# sch_camera.net
KiCad netlist of a schematic drawn in Altium Designer
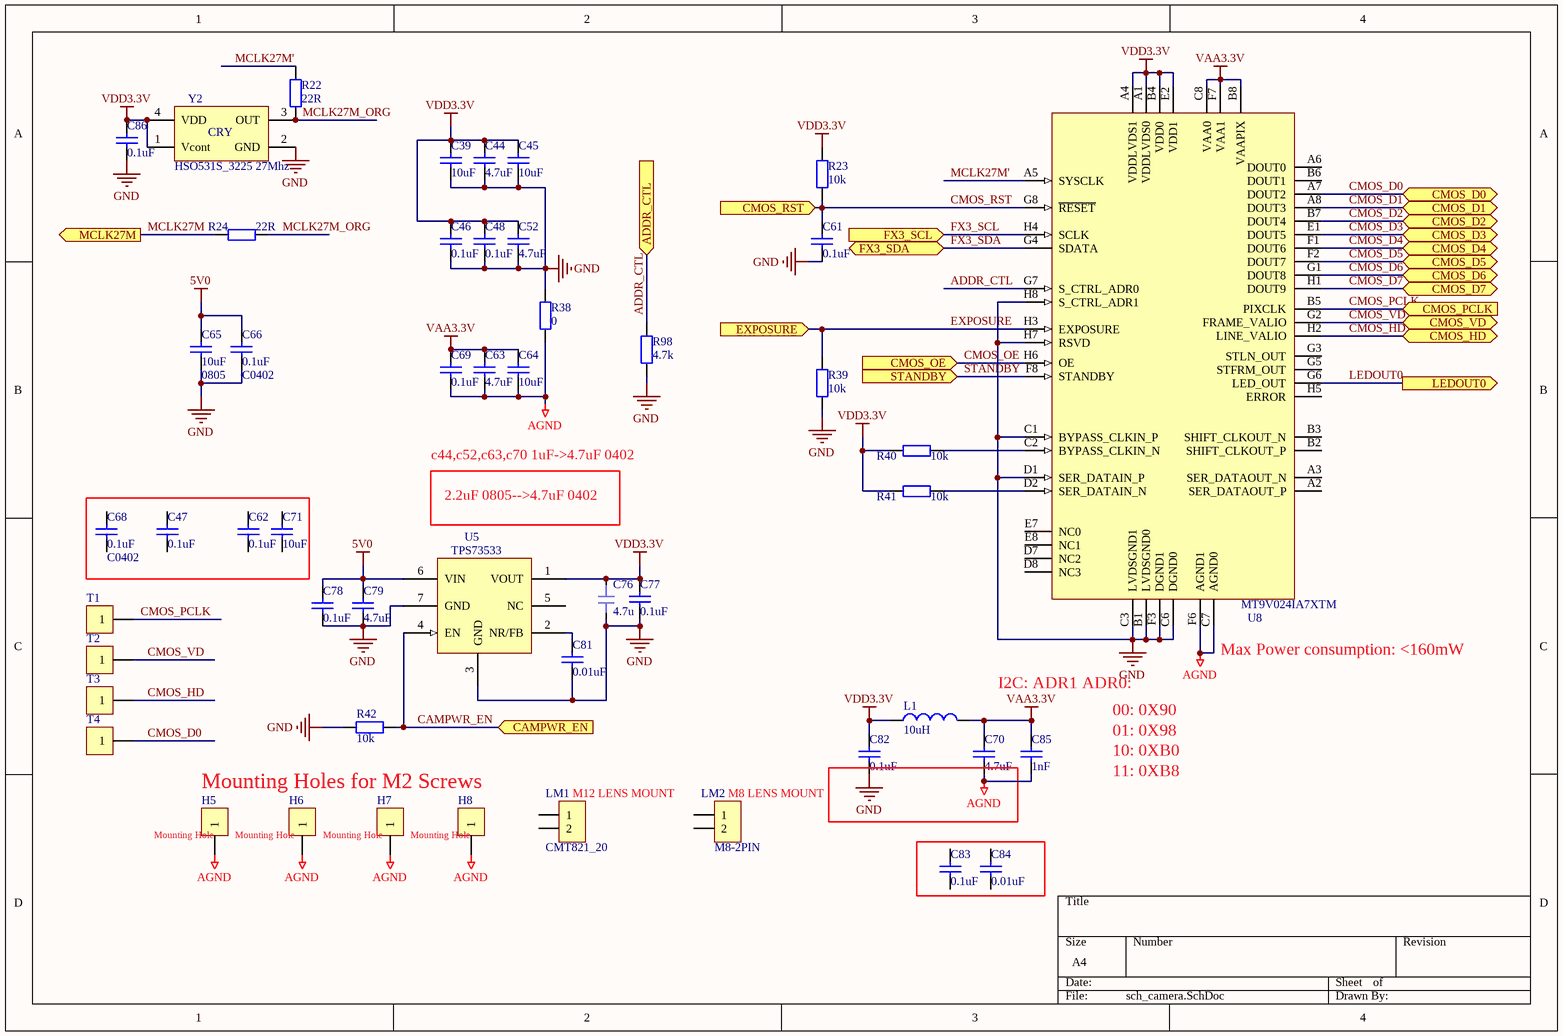
[diagram p0: sch_camera.SchDoc]

(export (version "E")
  (design (tool "Eeschema 10.0.6"))
  (components
    (comp (ref "C39")
      (value "10uF")
      (footprint "0805C")
      (description "Capacitor")
      (fields (field (name "PUBLISHER") "Altium Limited"))
      (libsource (lib "Miscellaneous Devices") (part "Cap"))
    )
    (comp (ref "C44")
      (value "4.7uF")
      (footprint "0402C")
      (description "Capacitor")
      (fields (field (name "PUBLISHER") "Altium Limited"))
      (libsource (lib "Miscellaneous Devices") (part "Cap"))
    )
    (comp (ref "C45")
      (value "10uF")
      (footprint "0805C")
      (description "Capacitor")
      (fields (field (name "PUBLISHER") "Altium Limited"))
      (libsource (lib "Miscellaneous Devices") (part "Cap"))
    )
    (comp (ref "C46")
      (value "0.1uF")
      (footprint "0402C")
      (description "Capacitor")
      (fields (field (name "PUBLISHER") "Altium Limited"))
      (libsource (lib "Miscellaneous Devices") (part "Cap"))
    )
    (comp (ref "C47")
      (value "0.1uF")
      (footprint "0402C")
      (description "Capacitor")
      (fields (field (name "PUBLISHER") "Altium Limited"))
      (libsource (lib "Miscellaneous Devices") (part "Cap"))
    )
    (comp (ref "C48")
      (value "0.1uF")
      (footprint "0402C")
      (description "Capacitor")
      (fields (field (name "PUBLISHER") "Altium Limited"))
      (libsource (lib "Miscellaneous Devices") (part "Cap"))
    )
    (comp (ref "C52")
      (value "4.7uF")
      (footprint "0402C")
      (description "Capacitor")
      (fields (field (name "PUBLISHER") "Altium Limited"))
      (libsource (lib "Miscellaneous Devices") (part "Cap"))
    )
    (comp (ref "C61")
      (value "0.1uF")
      (footprint "0402C_L")
      (description "Capacitor")
      (fields (field (name "PUBLISHER") "Altium Limited"))
      (libsource (lib "Miscellaneous Devices") (part "Cap"))
    )
    (comp (ref "C62")
      (value "0.1uF")
      (footprint "0402C")
      (description "Capacitor")
      (fields (field (name "PUBLISHER") "Altium Limited"))
      (libsource (lib "Miscellaneous Devices") (part "Cap"))
    )
    (comp (ref "C63")
      (value "4.7uF")
      (footprint "0402C")
      (description "Capacitor")
      (fields (field (name "PUBLISHER") "Altium Limited"))
      (libsource (lib "Miscellaneous Devices") (part "Cap"))
    )
    (comp (ref "C64")
      (value "10uF")
      (footprint "0805C")
      (description "Capacitor")
      (fields (field (name "PUBLISHER") "Altium Limited"))
      (libsource (lib "Miscellaneous Devices") (part "Cap"))
    )
    (comp (ref "C65")
      (value "10uF")
      (footprint "0805C")
      (description "Capacitor")
      (fields (field (name "ALTIUM_VALUE") "0805") (field (name "PUBLISHER") "Altium Limited"))
      (libsource (lib "Miscellaneous Devices") (part "Cap"))
    )
    (comp (ref "C66")
      (value "0.1uF")
      (footprint "0402C")
      (description "Capacitor")
      (fields (field (name "ALTIUM_VALUE") "C0402") (field (name "PUBLISHER") "Altium Limited"))
      (libsource (lib "Miscellaneous Devices") (part "Cap"))
    )
    (comp (ref "C68")
      (value "0.1uF")
      (footprint "0402C")
      (description "Capacitor")
      (fields (field (name "ALTIUM_VALUE") "C0402") (field (name "PUBLISHER") "Altium Limited"))
      (libsource (lib "Miscellaneous Devices") (part "Cap"))
    )
    (comp (ref "C69")
      (value "0.1uF")
      (footprint "0402C")
      (description "Capacitor")
      (fields (field (name "PUBLISHER") "Altium Limited"))
      (libsource (lib "Miscellaneous Devices") (part "Cap"))
    )
    (comp (ref "C70")
      (value "4.7uF")
      (footprint "0402C")
      (description "Capacitor")
      (fields (field (name "PUBLISHER") "Altium Limited"))
      (libsource (lib "Miscellaneous Devices") (part "Cap"))
    )
    (comp (ref "C71")
      (value "10uF")
      (footprint "0805C")
      (description "Capacitor")
      (fields (field (name "PUBLISHER") "Altium Limited"))
      (libsource (lib "Miscellaneous Devices") (part "Cap"))
    )
    (comp (ref "C76")
      (value "4.7u")
      (footprint "0402C_L")
      (description "CC0402MRX5R5BB475")
      (libsource (lib "V0P1") (part "cap0402"))
    )
    (comp (ref "C77")
      (value "0.1uF")
      (footprint "0402C_L")
      (description "Capacitor")
      (fields (field (name "PUBLISHER") "Altium Limited"))
      (libsource (lib "Miscellaneous Devices") (part "Cap"))
    )
    (comp (ref "C78")
      (value "0.1uF")
      (footprint "0402C")
      (description "Capacitor")
      (fields (field (name "PUBLISHER") "Altium Limited"))
      (libsource (lib "Miscellaneous Devices") (part "Cap"))
    )
    (comp (ref "C79")
      (value "4.7uF")
      (footprint "0402C_L")
      (description "Capacitor")
      (fields (field (name "Comment") "1uF") (field (name "PUBLISHER") "Altium Limited"))
      (libsource (lib "Miscellaneous Devices") (part "Cap"))
    )
    (comp (ref "C81")
      (value "0.01uF")
      (footprint "0402C_L")
      (description "Capacitor")
      (fields (field (name "PUBLISHER") "Altium Limited"))
      (libsource (lib "Miscellaneous Devices") (part "Cap"))
    )
    (comp (ref "C82")
      (value "0.1uF")
      (footprint "0402C_L")
      (description "Capacitor")
      (fields (field (name "PUBLISHER") "Altium Limited"))
      (libsource (lib "Miscellaneous Devices") (part "Cap"))
    )
    (comp (ref "C83")
      (value "0.1uF")
      (footprint "0402C_L")
      (description "Capacitor")
      (fields (field (name "PUBLISHER") "Altium Limited"))
      (libsource (lib "Miscellaneous Devices") (part "Cap"))
    )
    (comp (ref "C84")
      (value "0.01uF")
      (footprint "0402C_L")
      (description "Capacitor")
      (fields (field (name "PUBLISHER") "Altium Limited"))
      (libsource (lib "Miscellaneous Devices") (part "Cap"))
    )
    (comp (ref "C85")
      (value "1nF")
      (footprint "0402C_L")
      (description "Capacitor")
      (fields (field (name "PUBLISHER") "Altium Limited"))
      (libsource (lib "Miscellaneous Devices") (part "Cap"))
    )
    (comp (ref "C86")
      (value "0.1uF")
      (footprint "0402C_L")
      (description "Capacitor")
      (fields (field (name "PUBLISHER") "Altium Limited"))
      (libsource (lib "Miscellaneous Devices") (part "Cap"))
    )
    (comp (ref "H5")
      (value "CON1")
      (footprint "PAD_M3_D350_450")
      (description "Connector")
      (libsource (lib "SuperSchLib") (part "CON1"))
    )
    (comp (ref "H6")
      (value "CON1")
      (footprint "PAD_M3_D350_450")
      (description "Connector")
      (libsource (lib "SuperSchLib") (part "CON1"))
    )
    (comp (ref "H7")
      (value "CON1")
      (footprint "PAD_M3_D350_450")
      (description "Connector")
      (libsource (lib "SuperSchLib") (part "CON1"))
    )
    (comp (ref "H8")
      (value "CON1")
      (footprint "PAD_M3_D350_450")
      (description "Connector")
      (libsource (lib "SuperSchLib") (part "CON1"))
    )
    (comp (ref "L1")
      (value "10uH")
      (footprint "0805R")
      (description "Inductor")
      (libsource (lib "SWUST_ROBOT") (part "Inductor"))
    )
    (comp (ref "LM1")
      (value "CMT821_20")
      (footprint "PAD_M3_D350_450")
      (description "Connector")
      (libsource (lib "SuperSchLib") (part "CON2"))
    )
    (comp (ref "LM2")
      (value "M8-2PIN")
      (footprint "PAD_M3_D350_450")
      (description "Connector")
      (libsource (lib "SuperSchLib") (part "CON2"))
    )
    (comp (ref "R22")
      (value "22R")
      (footprint "0402R_L")
      (description "Resistor")
      (fields (field (name "Comment") "0R") (field (name "PUBLISHER") "Altium Limited"))
      (libsource (lib "") (part "Resistor_2"))
    )
    (comp (ref "R23")
      (value "10k")
      (footprint "0402R_L")
      (description "Resistor")
      (fields (field (name "Comment") "10K") (field (name "PUBLISHER") "Altium Limited"))
      (libsource (lib "") (part "Resistor_1"))
    )
    (comp (ref "R24")
      (value "22R")
      (footprint "0402R")
      (description "Resistor")
      (fields (field (name "PUBLISHER") "Altium Limited"))
      (libsource (lib "") (part "Resistor_3"))
    )
    (comp (ref "R38")
      (value "0")
      (footprint "0402R")
      (description "Resistor")
      (fields (field (name "Comment") "0R") (field (name "PUBLISHER") "Altium Limited"))
      (libsource (lib "") (part "Resistor_2"))
    )
    (comp (ref "R39")
      (value "10k")
      (footprint "0402R_L")
      (description "Resistor")
      (fields (field (name "Comment") "10K") (field (name "PUBLISHER") "Altium Limited"))
      (libsource (lib "") (part "Resistor_2"))
    )
    (comp (ref "R40")
      (value "10k")
      (footprint "0402R_L")
      (description "Resistor")
      (fields (field (name "Comment") "10K") (field (name "PUBLISHER") "Altium Limited"))
      (libsource (lib "SZG") (part "Resistor"))
    )
    (comp (ref "R41")
      (value "10k")
      (footprint "0402R_L")
      (description "Resistor")
      (fields (field (name "Comment") "10K") (field (name "PUBLISHER") "Altium Limited"))
      (libsource (lib "SZG") (part "Resistor"))
    )
    (comp (ref "R42")
      (value "10k")
      (footprint "0402R_L")
      (description "Resistor")
      (fields (field (name "Comment") "10K") (field (name "PUBLISHER") "Altium Limited"))
      (libsource (lib "SZG") (part "Resistor"))
    )
    (comp (ref "R98")
      (value "4.7k")
      (footprint "0402R_L")
      (description "Resistor")
      (fields (field (name "Comment") "4.7K") (field (name "PUBLISHER") "Altium Limited"))
      (libsource (lib "") (part "Resistor_1"))
    )
    (comp (ref "T1")
      (value "CON1")
      (footprint "PAD_TP_D1.2")
      (description "Connector")
      (libsource (lib "") (part "CON1_1"))
    )
    (comp (ref "T2")
      (value "CON1")
      (footprint "PAD_TP_D1.2")
      (description "Connector")
      (libsource (lib "") (part "CON1_1"))
    )
    (comp (ref "T3")
      (value "CON1")
      (footprint "PAD_TP_D1.2")
      (description "Connector")
      (libsource (lib "") (part "CON1_1"))
    )
    (comp (ref "T4")
      (value "CON1")
      (footprint "PAD_TP_D1.2")
      (description "Connector")
      (libsource (lib "") (part "CON1_1"))
    )
    (comp (ref "U5")
      (value "TPS73533")
      (footprint "SON6_P65L21W21H8_DRV")
      (libsource (lib "SZG") (part "TPS73533"))
    )
    (comp (ref "U8")
      (value "MT9V024IA7XTM")
      (footprint "IBGA52_8X8_P100L90W90H90R")
      (libsource (lib "SZG") (part "MT9V024IA7XTM"))
    )
    (comp (ref "Y2")
      (value "HSO531S_3225 27Mhz")
      (footprint "XTAL_3225")
      (description "有源晶振")
      (libsource (lib "超集元件库") (part "CRY"))
    )
  )
  (nets
    (net (code "1") (name "/ADDR_CTL") (class "Default")
      (node (ref "R98") (pin "2") (pinfunction "2_2") (pintype "passive"))
      (node (ref "U8") (pin "G7") (pinfunction "S_CTRL_ADR0_G7") (pintype "input"))
    )
    (net (code "2") (name "/CAMPWR_EN") (class "Default")
      (node (ref "R42") (pin "1") (pinfunction "1_1") (pintype "passive"))
      (node (ref "U5") (pin "4") (pinfunction "EN_4") (pintype "input"))
    )
    (net (code "3") (name "/CMOS_D0") (class "Default")
      (node (ref "T4") (pin "1") (pinfunction "1_1") (pintype "passive"))
      (node (ref "U8") (pin "A7") (pinfunction "DOUT2_A7") (pintype "passive"))
    )
    (net (code "4") (name "/CMOS_D1") (class "Default")
      (node (ref "U8") (pin "A8") (pinfunction "DOUT3_A8") (pintype "passive"))
    )
    (net (code "5") (name "/CMOS_D2") (class "Default")
      (node (ref "U8") (pin "B7") (pinfunction "DOUT4_B7") (pintype "passive"))
    )
    (net (code "6") (name "/CMOS_D3") (class "Default")
      (node (ref "U8") (pin "E1") (pinfunction "DOUT5_E1") (pintype "passive"))
    )
    (net (code "7") (name "/CMOS_D4") (class "Default")
      (node (ref "U8") (pin "F1") (pinfunction "DOUT6_F1") (pintype "passive"))
    )
    (net (code "8") (name "/CMOS_D5") (class "Default")
      (node (ref "U8") (pin "F2") (pinfunction "DOUT7_F2") (pintype "passive"))
    )
    (net (code "9") (name "/CMOS_D6") (class "Default")
      (node (ref "U8") (pin "G1") (pinfunction "DOUT8_G1") (pintype "passive"))
    )
    (net (code "10") (name "/CMOS_D7") (class "Default")
      (node (ref "U8") (pin "H1") (pinfunction "DOUT9_H1") (pintype "passive"))
    )
    (net (code "11") (name "/CMOS_HD") (class "Default")
      (node (ref "T3") (pin "1") (pinfunction "1_1") (pintype "passive"))
      (node (ref "U8") (pin "H2") (pinfunction "LINE_VALIO_H2") (pintype "passive"))
    )
    (net (code "12") (name "/CMOS_OE") (class "Default")
      (node (ref "U8") (pin "H6") (pinfunction "OE_H6") (pintype "input"))
    )
    (net (code "13") (name "/CMOS_PCLK") (class "Default")
      (node (ref "T1") (pin "1") (pinfunction "1_1") (pintype "passive"))
      (node (ref "U8") (pin "B5") (pinfunction "PIXCLK_B5") (pintype "passive"))
    )
    (net (code "14") (name "/CMOS_RST") (class "Default")
      (node (ref "C61") (pin "2") (pinfunction "2_2") (pintype "passive"))
      (node (ref "R23") (pin "1") (pinfunction "1_1") (pintype "passive"))
      (node (ref "U8") (pin "G8") (pinfunction "~{RESET}_G8") (pintype "input"))
    )
    (net (code "15") (name "/CMOS_VD") (class "Default")
      (node (ref "T2") (pin "1") (pinfunction "1_1") (pintype "passive"))
      (node (ref "U8") (pin "G2") (pinfunction "FRAME_VALIO_G2") (pintype "passive"))
    )
    (net (code "16") (name "/EXPOSURE") (class "Default")
      (node (ref "R39") (pin "1") (pinfunction "1_1") (pintype "passive"))
      (node (ref "U8") (pin "H3") (pinfunction "EXPOSURE_H3") (pintype "input"))
    )
    (net (code "17") (name "/FX3_SCL") (class "Default")
      (node (ref "U8") (pin "H4") (pinfunction "SCLK_H4") (pintype "input"))
    )
    (net (code "18") (name "/FX3_SDA") (class "Default")
      (node (ref "U8") (pin "G4") (pinfunction "SDATA_G4") (pintype "passive"))
    )
    (net (code "19") (name "/LEDOUT0") (class "Default")
      (node (ref "U8") (pin "G6") (pinfunction "LED_OUT_G6") (pintype "passive"))
    )
    (net (code "20") (name "/MCLK27M") (class "Default")
      (node (ref "R24") (pin "1") (pinfunction "1_1") (pintype "passive"))
    )
    (net (code "21") (name "/MCLK27M'") (class "Default")
      (node (ref "R22") (pin "1") (pinfunction "1_1") (pintype "passive"))
      (node (ref "U8") (pin "A5") (pinfunction "SYSCLK_A5") (pintype "input"))
    )
    (net (code "22") (name "/MCLK27M_ORG") (class "Default")
      (node (ref "R22") (pin "2") (pinfunction "2_2") (pintype "passive"))
      (node (ref "R24") (pin "2") (pinfunction "2_2") (pintype "passive"))
      (node (ref "Y2") (pin "3") (pinfunction "OUT_3") (pintype "passive"))
    )
    (net (code "23") (name "/STANDBY") (class "Default")
      (node (ref "U8") (pin "F8") (pinfunction "STANDBY_F8") (pintype "input"))
    )
    (net (code "24") (name "5V0") (class "Default")
      (node (ref "C65") (pin "2") (pinfunction "2_2") (pintype "passive"))
      (node (ref "C66") (pin "2") (pinfunction "2_2") (pintype "passive"))
      (node (ref "C78") (pin "2") (pinfunction "2_2") (pintype "passive"))
      (node (ref "C79") (pin "2") (pinfunction "2_2") (pintype "passive"))
      (node (ref "U5") (pin "6") (pinfunction "VIN_6") (pintype "passive"))
    )
    (net (code "25") (name "AGND") (class "Default")
      (node (ref "C63") (pin "1") (pinfunction "1_1") (pintype "passive"))
      (node (ref "C64") (pin "1") (pinfunction "1_1") (pintype "passive"))
      (node (ref "C69") (pin "1") (pinfunction "1_1") (pintype "passive"))
      (node (ref "C70") (pin "1") (pinfunction "1_1") (pintype "passive"))
      (node (ref "C85") (pin "1") (pinfunction "1_1") (pintype "passive"))
      (node (ref "H5") (pin "1") (pinfunction "1_1") (pintype "passive"))
      (node (ref "H6") (pin "1") (pinfunction "1_1") (pintype "passive"))
      (node (ref "H7") (pin "1") (pinfunction "1_1") (pintype "passive"))
      (node (ref "H8") (pin "1") (pinfunction "1_1") (pintype "passive"))
      (node (ref "R38") (pin "2") (pinfunction "2_2") (pintype "passive"))
      (node (ref "U8") (pin "C7") (pinfunction "AGND0_C7") (pintype "power_in"))
      (node (ref "U8") (pin "F6") (pinfunction "AGND1_F6") (pintype "power_in"))
    )
    (net (code "26") (name "GND") (class "Default")
      (node (ref "C39") (pin "1") (pinfunction "1_1") (pintype "passive"))
      (node (ref "C44") (pin "1") (pinfunction "1_1") (pintype "passive"))
      (node (ref "C45") (pin "1") (pinfunction "1_1") (pintype "passive"))
      (node (ref "C46") (pin "1") (pinfunction "1_1") (pintype "passive"))
      (node (ref "C48") (pin "1") (pinfunction "1_1") (pintype "passive"))
      (node (ref "C52") (pin "1") (pinfunction "1_1") (pintype "passive"))
      (node (ref "C61") (pin "1") (pinfunction "1_1") (pintype "passive"))
      (node (ref "C65") (pin "1") (pinfunction "1_1") (pintype "passive"))
      (node (ref "C66") (pin "1") (pinfunction "1_1") (pintype "passive"))
      (node (ref "C76") (pin "2") (pinfunction "2_2") (pintype "passive"))
      (node (ref "C77") (pin "1") (pinfunction "1_1") (pintype "passive"))
      (node (ref "C78") (pin "1") (pinfunction "1_1") (pintype "passive"))
      (node (ref "C79") (pin "1") (pinfunction "1_1") (pintype "passive"))
      (node (ref "C81") (pin "1") (pinfunction "1_1") (pintype "passive"))
      (node (ref "C82") (pin "1") (pinfunction "1_1") (pintype "passive"))
      (node (ref "C86") (pin "1") (pinfunction "1_1") (pintype "passive"))
      (node (ref "R38") (pin "1") (pinfunction "1_1") (pintype "passive"))
      (node (ref "R39") (pin "2") (pinfunction "2_2") (pintype "passive"))
      (node (ref "R42") (pin "2") (pinfunction "2_2") (pintype "passive"))
      (node (ref "R98") (pin "1") (pinfunction "1_1") (pintype "passive"))
      (node (ref "U5") (pin "3") (pinfunction "GND_3") (pintype "passive"))
      (node (ref "U5") (pin "7") (pinfunction "GND_7") (pintype "passive"))
      (node (ref "U8") (pin "B1") (pinfunction "LVDSGND0_B1") (pintype "power_in"))
      (node (ref "U8") (pin "C1") (pinfunction "BYPASS_CLKIN_P_C1") (pintype "input"))
      (node (ref "U8") (pin "C3") (pinfunction "LVDSGND1_C3") (pintype "power_in"))
      (node (ref "U8") (pin "C6") (pinfunction "DGND0_C6") (pintype "power_in"))
      (node (ref "U8") (pin "D1") (pinfunction "SER_DATAIN_P_D1") (pintype "input"))
      (node (ref "U8") (pin "F3") (pinfunction "DGND1_F3") (pintype "power_in"))
      (node (ref "U8") (pin "H7") (pinfunction "RSVD_H7") (pintype "input"))
      (node (ref "U8") (pin "H8") (pinfunction "S_CTRL_ADR1_H8") (pintype "input"))
      (node (ref "Y2") (pin "2") (pinfunction "GND_2") (pintype "passive"))
    )
    (net (code "27") (name "Net-(U5-NR{slash}FB)") (class "Default")
      (node (ref "C81") (pin "2") (pinfunction "2_2") (pintype "passive"))
      (node (ref "U5") (pin "2") (pinfunction "NR/FB_2") (pintype "passive"))
    )
    (net (code "28") (name "Net-(U8-BYPASS_CLKIN_N)") (class "Default")
      (node (ref "R40") (pin "1") (pinfunction "1_1") (pintype "passive"))
      (node (ref "U8") (pin "C2") (pinfunction "BYPASS_CLKIN_N_C2") (pintype "input"))
    )
    (net (code "29") (name "Net-(U8-SER_DATAIN_N)") (class "Default")
      (node (ref "R41") (pin "1") (pinfunction "1_1") (pintype "passive"))
      (node (ref "U8") (pin "D2") (pinfunction "SER_DATAIN_N_D2") (pintype "input"))
    )
    (net (code "30") (name "VAA3.3V") (class "Default")
      (node (ref "C63") (pin "2") (pinfunction "2_2") (pintype "passive"))
      (node (ref "C64") (pin "2") (pinfunction "2_2") (pintype "passive"))
      (node (ref "C69") (pin "2") (pinfunction "2_2") (pintype "passive"))
      (node (ref "C70") (pin "2") (pinfunction "2_2") (pintype "passive"))
      (node (ref "C85") (pin "2") (pinfunction "2_2") (pintype "passive"))
      (node (ref "L1") (pin "2") (pinfunction "2_2") (pintype "passive"))
      (node (ref "U8") (pin "B8") (pinfunction "VAAPIX_B8") (pintype "power_in"))
      (node (ref "U8") (pin "C8") (pinfunction "VAA0_C8") (pintype "power_in"))
      (node (ref "U8") (pin "F7") (pinfunction "VAA1_F7") (pintype "power_in"))
    )
    (net (code "31") (name "VDD3.3V") (class "Default")
      (node (ref "C39") (pin "2") (pinfunction "2_2") (pintype "passive"))
      (node (ref "C44") (pin "2") (pinfunction "2_2") (pintype "passive"))
      (node (ref "C45") (pin "2") (pinfunction "2_2") (pintype "passive"))
      (node (ref "C46") (pin "2") (pinfunction "2_2") (pintype "passive"))
      (node (ref "C48") (pin "2") (pinfunction "2_2") (pintype "passive"))
      (node (ref "C52") (pin "2") (pinfunction "2_2") (pintype "passive"))
      (node (ref "C76") (pin "1") (pinfunction "1_1") (pintype "passive"))
      (node (ref "C77") (pin "2") (pinfunction "2_2") (pintype "passive"))
      (node (ref "C82") (pin "2") (pinfunction "2_2") (pintype "passive"))
      (node (ref "C86") (pin "2") (pinfunction "2_2") (pintype "passive"))
      (node (ref "L1") (pin "1") (pinfunction "1_1") (pintype "passive"))
      (node (ref "R23") (pin "2") (pinfunction "2_2") (pintype "passive"))
      (node (ref "R40") (pin "2") (pinfunction "2_2") (pintype "passive"))
      (node (ref "R41") (pin "2") (pinfunction "2_2") (pintype "passive"))
      (node (ref "U5") (pin "1") (pinfunction "VOUT_1") (pintype "passive"))
      (node (ref "U8") (pin "A1") (pinfunction "VDDLVDS0_A1") (pintype "power_in"))
      (node (ref "U8") (pin "A4") (pinfunction "VDDLVDS1_A4") (pintype "power_in"))
      (node (ref "U8") (pin "B4") (pinfunction "VDD0_B4") (pintype "power_in"))
      (node (ref "U8") (pin "E2") (pinfunction "VDD1_E2") (pintype "power_in"))
      (node (ref "Y2") (pin "1") (pinfunction "Vcont_1") (pintype "passive"))
      (node (ref "Y2") (pin "4") (pinfunction "VDD_4") (pintype "passive"))
    )
    (net (code "32") (name "unconnected-(C47-Pad1)") (class "Default")
      (node (ref "C47") (pin "1") (pinfunction "1_1") (pintype "passive"))
    )
    (net (code "33") (name "unconnected-(C47-Pad2)") (class "Default")
      (node (ref "C47") (pin "2") (pinfunction "2_2") (pintype "passive"))
    )
    (net (code "34") (name "unconnected-(C62-Pad1)") (class "Default")
      (node (ref "C62") (pin "1") (pinfunction "1_1") (pintype "passive"))
    )
    (net (code "35") (name "unconnected-(C62-Pad2)") (class "Default")
      (node (ref "C62") (pin "2") (pinfunction "2_2") (pintype "passive"))
    )
    (net (code "36") (name "unconnected-(C68-Pad1)") (class "Default")
      (node (ref "C68") (pin "1") (pinfunction "1_1") (pintype "passive"))
    )
    (net (code "37") (name "unconnected-(C68-Pad2)") (class "Default")
      (node (ref "C68") (pin "2") (pinfunction "2_2") (pintype "passive"))
    )
    (net (code "38") (name "unconnected-(C71-Pad1)") (class "Default")
      (node (ref "C71") (pin "1") (pinfunction "1_1") (pintype "passive"))
    )
    (net (code "39") (name "unconnected-(C71-Pad2)") (class "Default")
      (node (ref "C71") (pin "2") (pinfunction "2_2") (pintype "passive"))
    )
    (net (code "40") (name "unconnected-(C83-Pad1)") (class "Default")
      (node (ref "C83") (pin "1") (pinfunction "1_1") (pintype "passive"))
    )
    (net (code "41") (name "unconnected-(C83-Pad2)") (class "Default")
      (node (ref "C83") (pin "2") (pinfunction "2_2") (pintype "passive"))
    )
    (net (code "42") (name "unconnected-(C84-Pad1)") (class "Default")
      (node (ref "C84") (pin "1") (pinfunction "1_1") (pintype "passive"))
    )
    (net (code "43") (name "unconnected-(C84-Pad2)") (class "Default")
      (node (ref "C84") (pin "2") (pinfunction "2_2") (pintype "passive"))
    )
    (net (code "44") (name "unconnected-(LM1-Pad1)") (class "Default")
      (node (ref "LM1") (pin "1") (pinfunction "1_1") (pintype "passive"))
    )
    (net (code "45") (name "unconnected-(LM1-Pad2)") (class "Default")
      (node (ref "LM1") (pin "2") (pinfunction "2_2") (pintype "passive"))
    )
    (net (code "46") (name "unconnected-(LM2-Pad1)") (class "Default")
      (node (ref "LM2") (pin "1") (pinfunction "1_1") (pintype "passive"))
    )
    (net (code "47") (name "unconnected-(LM2-Pad2)") (class "Default")
      (node (ref "LM2") (pin "2") (pinfunction "2_2") (pintype "passive"))
    )
    (net (code "48") (name "unconnected-(U5-NC-Pad5)") (class "Default")
      (node (ref "U5") (pin "5") (pinfunction "NC_5") (pintype "passive"))
    )
    (net (code "49") (name "unconnected-(U8-DOUT0-PadA6)") (class "Default")
      (node (ref "U8") (pin "A6") (pinfunction "DOUT0_A6") (pintype "passive"))
    )
    (net (code "50") (name "unconnected-(U8-DOUT1-PadB6)") (class "Default")
      (node (ref "U8") (pin "B6") (pinfunction "DOUT1_B6") (pintype "passive"))
    )
    (net (code "51") (name "unconnected-(U8-ERROR-PadH5)") (class "Default")
      (node (ref "U8") (pin "H5") (pinfunction "ERROR_H5") (pintype "passive"))
    )
    (net (code "52") (name "unconnected-(U8-NC0-PadE7)") (class "Default")
      (node (ref "U8") (pin "E7") (pinfunction "NC0_E7") (pintype "passive"))
    )
    (net (code "53") (name "unconnected-(U8-NC1-PadE8)") (class "Default")
      (node (ref "U8") (pin "E8") (pinfunction "NC1_E8") (pintype "power_in"))
    )
    (net (code "54") (name "unconnected-(U8-NC2-PadD7)") (class "Default")
      (node (ref "U8") (pin "D7") (pinfunction "NC2_D7") (pintype "power_in"))
    )
    (net (code "55") (name "unconnected-(U8-NC3-PadD8)") (class "Default")
      (node (ref "U8") (pin "D8") (pinfunction "NC3_D8") (pintype "power_in"))
    )
    (net (code "56") (name "unconnected-(U8-SER_DATAOUT_N-PadA3)") (class "Default")
      (node (ref "U8") (pin "A3") (pinfunction "SER_DATAOUT_N_A3") (pintype "passive"))
    )
    (net (code "57") (name "unconnected-(U8-SER_DATAOUT_P-PadA2)") (class "Default")
      (node (ref "U8") (pin "A2") (pinfunction "SER_DATAOUT_P_A2") (pintype "passive"))
    )
    (net (code "58") (name "unconnected-(U8-SHIFT_CLKOUT_N-PadB3)") (class "Default")
      (node (ref "U8") (pin "B3") (pinfunction "SHIFT_CLKOUT_N_B3") (pintype "passive"))
    )
    (net (code "59") (name "unconnected-(U8-SHIFT_CLKOUT_P-PadB2)") (class "Default")
      (node (ref "U8") (pin "B2") (pinfunction "SHIFT_CLKOUT_P_B2") (pintype "passive"))
    )
    (net (code "60") (name "unconnected-(U8-STFRM_OUT-PadG5)") (class "Default")
      (node (ref "U8") (pin "G5") (pinfunction "STFRM_OUT_G5") (pintype "passive"))
    )
    (net (code "61") (name "unconnected-(U8-STLN_OUT-PadG3)") (class "Default")
      (node (ref "U8") (pin "G3") (pinfunction "STLN_OUT_G3") (pintype "passive"))
    )
  )
)
